# xbr.net
KiCad netlist of a schematic drawn in EAGLE
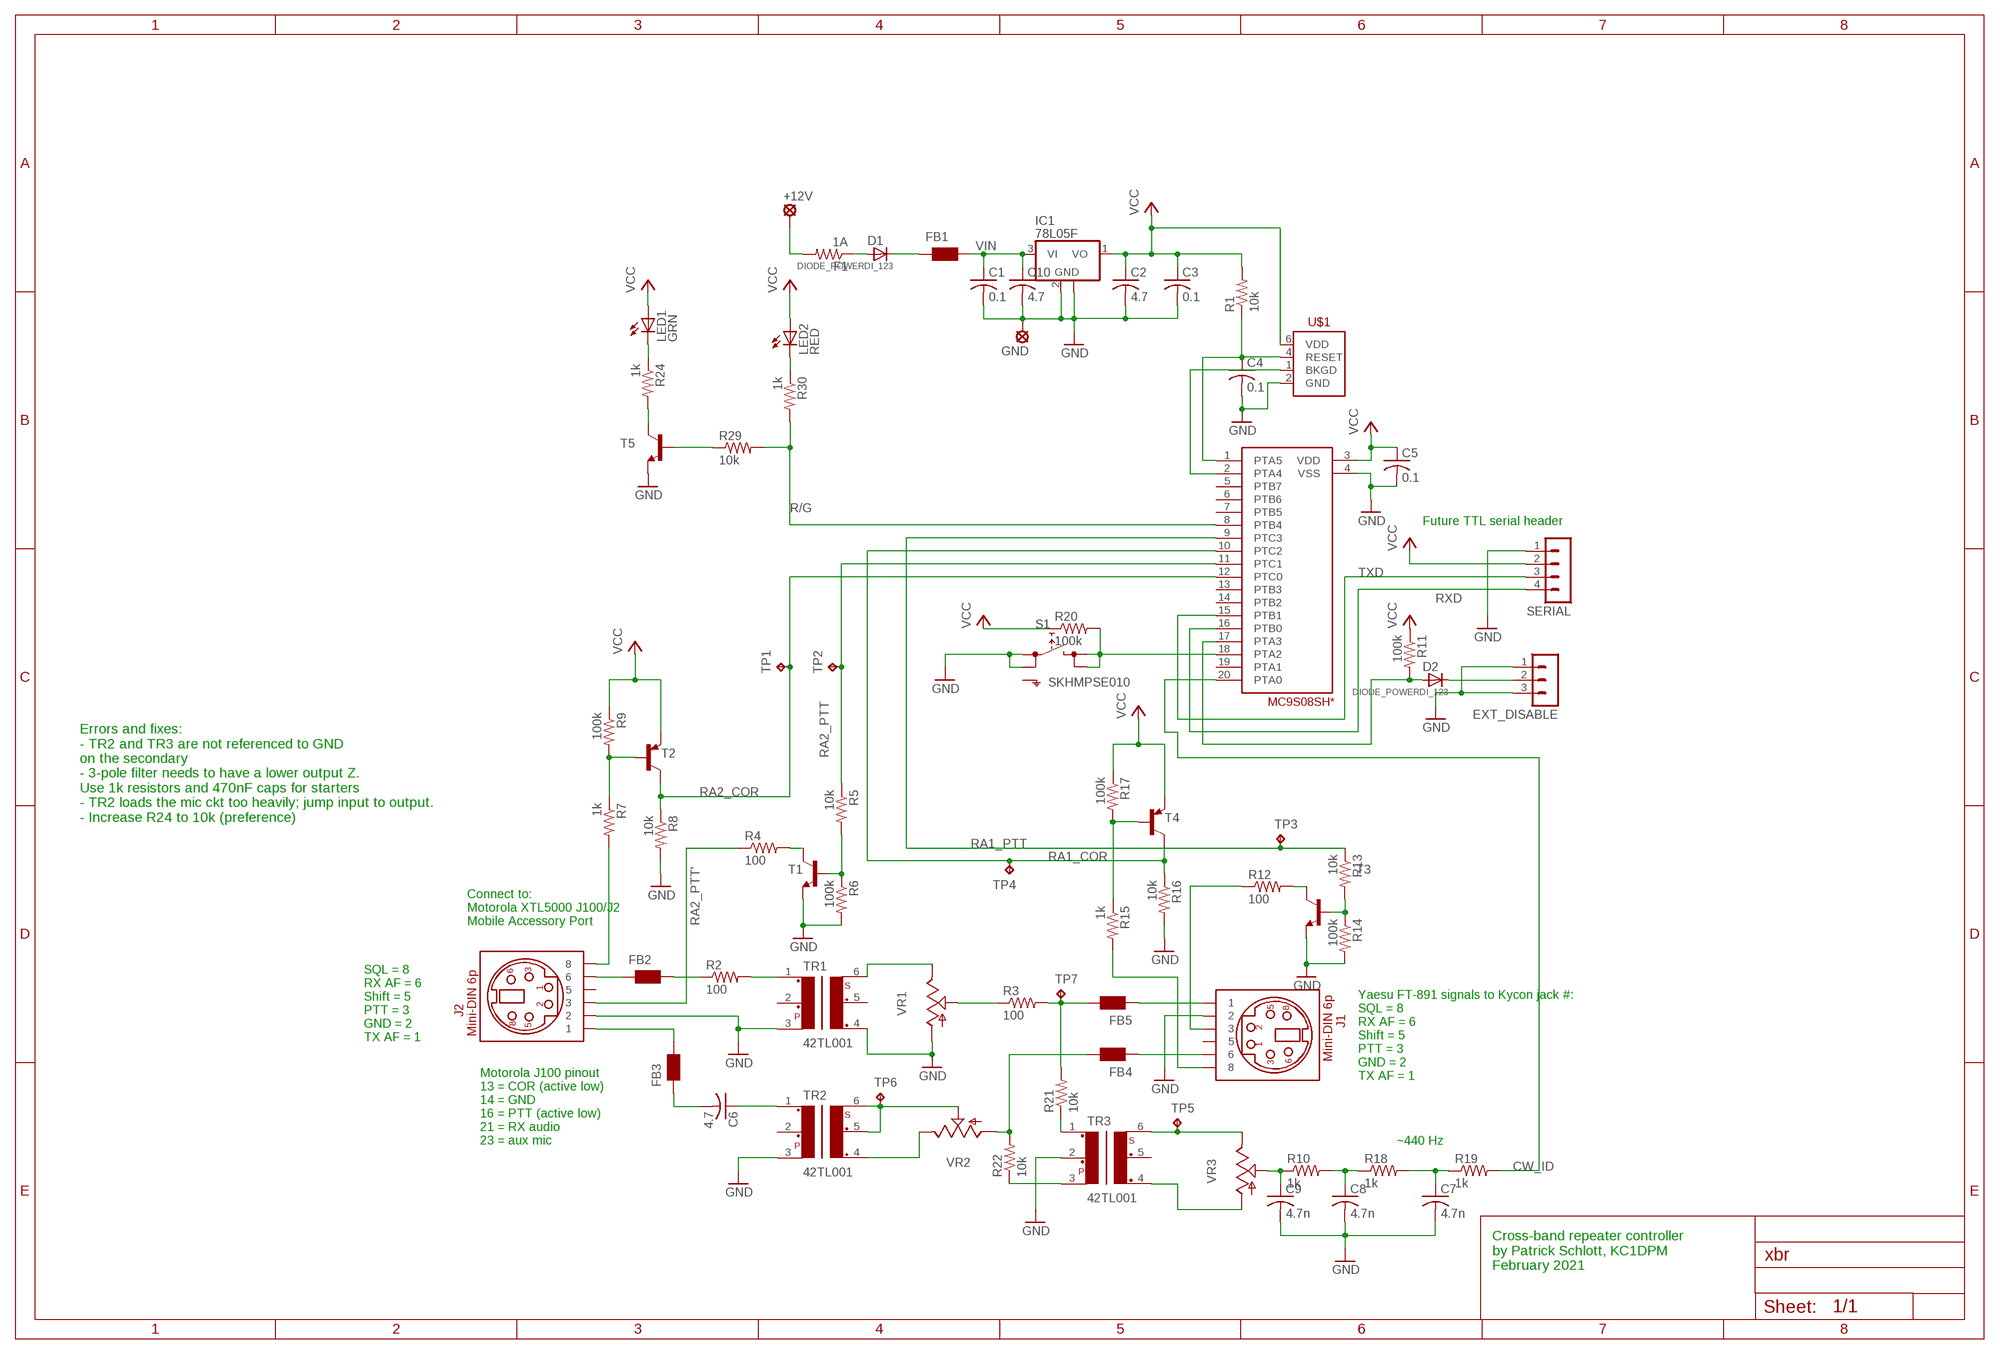
[diagram p0: schematic, sheet 1]

(export (version "E")
  (design (tool "Eeschema 10.0.6"))
  (components
    (comp (ref "+12V")
      (value "LSP10")
      (footprint "eagle-import:LSP10")
      (libsource (lib "eagle-import") (part "LSP10"))
    )
    (comp (ref "C1")
      (value "0.1")
      (footprint "eagle-import:C0603")
      (libsource (lib "eagle-import") (part "C-USC0603"))
    )
    (comp (ref "C2")
      (value "4.7")
      (footprint "eagle-import:C0805")
      (libsource (lib "eagle-import") (part "C-USC0805"))
    )
    (comp (ref "C3")
      (value "0.1")
      (footprint "eagle-import:C0603")
      (libsource (lib "eagle-import") (part "C-USC0603"))
    )
    (comp (ref "C4")
      (value "0.1")
      (footprint "eagle-import:C0603")
      (libsource (lib "eagle-import") (part "C-USC0603"))
    )
    (comp (ref "C5")
      (value "0.1")
      (footprint "eagle-import:C0603")
      (libsource (lib "eagle-import") (part "C-USC0603"))
    )
    (comp (ref "C6")
      (value "4.7")
      (footprint "eagle-import:C0805")
      (libsource (lib "eagle-import") (part "C-USC0805"))
    )
    (comp (ref "C7")
      (value "4.7n")
      (footprint "eagle-import:C0603")
      (libsource (lib "eagle-import") (part "C-USC0603"))
    )
    (comp (ref "C8")
      (value "4.7n")
      (footprint "eagle-import:C0603")
      (libsource (lib "eagle-import") (part "C-USC0603"))
    )
    (comp (ref "C9")
      (value "4.7n")
      (footprint "eagle-import:C0603")
      (libsource (lib "eagle-import") (part "C-USC0603"))
    )
    (comp (ref "C10")
      (value "4.7")
      (footprint "eagle-import:C0805")
      (libsource (lib "eagle-import") (part "C-USC0805"))
    )
    (comp (ref "D1")
      (value "DIODE_POWERDI_123")
      (footprint "eagle-import:POWERDI_123")
      (libsource (lib "eagle-import") (part "DIODE_POWERDI_123"))
    )
    (comp (ref "D2")
      (value "DIODE_POWERDI_123")
      (footprint "eagle-import:POWERDI_123")
      (libsource (lib "eagle-import") (part "DIODE_POWERDI_123"))
    )
    (comp (ref "EXT_DISABLE")
      (value "MA03-1")
      (footprint "eagle-import:MA03-1")
      (libsource (lib "eagle-import") (part "MA03-1"))
    )
    (comp (ref "F1")
      (value "1A")
      (footprint "eagle-import:R0603")
      (libsource (lib "eagle-import") (part "R-US_R0603"))
    )
    (comp (ref "FB1")
      (value "WE-CBF_0805")
      (footprint "eagle-import:0805")
      (libsource (lib "eagle-import") (part "WE-CBF_0805"))
    )
    (comp (ref "FB2")
      (value "WE-CBF_0805")
      (footprint "eagle-import:0805")
      (libsource (lib "eagle-import") (part "WE-CBF_0805"))
    )
    (comp (ref "FB3")
      (value "WE-CBF_0805")
      (footprint "eagle-import:0805")
      (libsource (lib "eagle-import") (part "WE-CBF_0805"))
    )
    (comp (ref "FB4")
      (value "WE-CBF_0805")
      (footprint "eagle-import:0805")
      (libsource (lib "eagle-import") (part "WE-CBF_0805"))
    )
    (comp (ref "FB5")
      (value "WE-CBF_0805")
      (footprint "eagle-import:0805")
      (libsource (lib "eagle-import") (part "WE-CBF_0805"))
    )
    (comp (ref "GND")
      (value "LSP10")
      (footprint "eagle-import:LSP10")
      (libsource (lib "eagle-import") (part "LSP10"))
    )
    (comp (ref "IC1")
      (value "78L05F")
      (footprint "eagle-import:SOT89")
      (libsource (lib "eagle-import") (part "78LF05"))
    )
    (comp (ref "J1")
      (value "MINIDIN-6P")
      (footprint "eagle-import:KMDTX-HT-6S-BSC")
      (libsource (lib "eagle-import") (part "MINIDIN-6P"))
    )
    (comp (ref "J2")
      (value "MINIDIN-6P")
      (footprint "eagle-import:KMDTX-HT-6S-BSC")
      (libsource (lib "eagle-import") (part "MINIDIN-6P"))
    )
    (comp (ref "LED1")
      (value "GRN")
      (footprint "eagle-import:CHIPLED_0603")
      (libsource (lib "eagle-import") (part "LEDCHIPLED_0603"))
    )
    (comp (ref "LED2")
      (value "RED")
      (footprint "eagle-import:CHIPLED_0805")
      (libsource (lib "eagle-import") (part "LEDCHIPLED_0805"))
    )
    (comp (ref "R1")
      (value "10k")
      (footprint "eagle-import:R0603")
      (libsource (lib "eagle-import") (part "R-US_R0603"))
    )
    (comp (ref "R2")
      (value "100")
      (footprint "eagle-import:R1206")
      (libsource (lib "eagle-import") (part "R-US_R1206"))
    )
    (comp (ref "R3")
      (value "100")
      (footprint "eagle-import:R1206")
      (libsource (lib "eagle-import") (part "R-US_R1206"))
    )
    (comp (ref "R4")
      (value "100")
      (footprint "eagle-import:R1206")
      (libsource (lib "eagle-import") (part "R-US_R1206"))
    )
    (comp (ref "R5")
      (value "10k")
      (footprint "eagle-import:R0603")
      (libsource (lib "eagle-import") (part "R-US_R0603"))
    )
    (comp (ref "R6")
      (value "100k")
      (footprint "eagle-import:R0603")
      (libsource (lib "eagle-import") (part "R-US_R0603"))
    )
    (comp (ref "R7")
      (value "1k")
      (footprint "eagle-import:R0603")
      (libsource (lib "eagle-import") (part "R-US_R0603"))
    )
    (comp (ref "R8")
      (value "10k")
      (footprint "eagle-import:R0603")
      (libsource (lib "eagle-import") (part "R-US_R0603"))
    )
    (comp (ref "R9")
      (value "100k")
      (footprint "eagle-import:R0603")
      (libsource (lib "eagle-import") (part "R-US_R0603"))
    )
    (comp (ref "R10")
      (value "1k")
      (footprint "eagle-import:R0603")
      (libsource (lib "eagle-import") (part "R-US_R0603"))
    )
    (comp (ref "R11")
      (value "100k")
      (footprint "eagle-import:R0603")
      (libsource (lib "eagle-import") (part "R-US_R0603"))
    )
    (comp (ref "R12")
      (value "100")
      (footprint "eagle-import:R1206")
      (libsource (lib "eagle-import") (part "R-US_R1206"))
    )
    (comp (ref "R13")
      (value "10k")
      (footprint "eagle-import:R0603")
      (libsource (lib "eagle-import") (part "R-US_R0603"))
    )
    (comp (ref "R14")
      (value "100k")
      (footprint "eagle-import:R0603")
      (libsource (lib "eagle-import") (part "R-US_R0603"))
    )
    (comp (ref "R15")
      (value "1k")
      (footprint "eagle-import:R0603")
      (libsource (lib "eagle-import") (part "R-US_R0603"))
    )
    (comp (ref "R16")
      (value "10k")
      (footprint "eagle-import:R0603")
      (libsource (lib "eagle-import") (part "R-US_R0603"))
    )
    (comp (ref "R17")
      (value "100k")
      (footprint "eagle-import:R0603")
      (libsource (lib "eagle-import") (part "R-US_R0603"))
    )
    (comp (ref "R18")
      (value "1k")
      (footprint "eagle-import:R0603")
      (libsource (lib "eagle-import") (part "R-US_R0603"))
    )
    (comp (ref "R19")
      (value "1k")
      (footprint "eagle-import:R0603")
      (libsource (lib "eagle-import") (part "R-US_R0603"))
    )
    (comp (ref "R20")
      (value "100k")
      (footprint "eagle-import:R0603")
      (libsource (lib "eagle-import") (part "R-US_R0603"))
    )
    (comp (ref "R21")
      (value "10k")
      (footprint "eagle-import:R0603")
      (libsource (lib "eagle-import") (part "R-US_R0603"))
    )
    (comp (ref "R22")
      (value "10k")
      (footprint "eagle-import:R0603")
      (libsource (lib "eagle-import") (part "R-US_R0603"))
    )
    (comp (ref "R24")
      (value "1k")
      (footprint "eagle-import:R0603")
      (libsource (lib "eagle-import") (part "R-US_R0603"))
    )
    (comp (ref "R29")
      (value "10k")
      (footprint "eagle-import:R0603")
      (libsource (lib "eagle-import") (part "R-US_R0603"))
    )
    (comp (ref "R30")
      (value "1k")
      (footprint "eagle-import:R0603")
      (libsource (lib "eagle-import") (part "R-US_R0603"))
    )
    (comp (ref "S1")
      (value "SKHMPSE010")
      (footprint "eagle-import:SKHMPXE010")
      (libsource (lib "eagle-import") (part "SKHMPE010S"))
    )
    (comp (ref "SERIAL")
      (value "MA04-1")
      (footprint "eagle-import:MA04-1")
      (libsource (lib "eagle-import") (part "MA04-1"))
    )
    (comp (ref "T1")
      (value "MMBT2222ALT1-NPN-SOT23-BEC")
      (footprint "eagle-import:SOT23-BEC")
      (libsource (lib "eagle-import") (part "-NPN-SOT23-BECMMBT2222ALT1"))
    )
    (comp (ref "T2")
      (value "MMBT3906LT1-PNP-SOT23-BEC")
      (footprint "eagle-import:SOT23-BEC")
      (libsource (lib "eagle-import") (part "-PNP-SOT23-BECMMBT3906LT1"))
    )
    (comp (ref "T3")
      (value "MMBT2222ALT1-NPN-SOT23-BEC")
      (footprint "eagle-import:SOT23-BEC")
      (libsource (lib "eagle-import") (part "-NPN-SOT23-BECMMBT2222ALT1"))
    )
    (comp (ref "T4")
      (value "MMBT3906LT1-PNP-SOT23-BEC")
      (footprint "eagle-import:SOT23-BEC")
      (libsource (lib "eagle-import") (part "-PNP-SOT23-BECMMBT3906LT1"))
    )
    (comp (ref "T5")
      (value "MMBT2222ALT1-NPN-SOT23-BEC")
      (footprint "eagle-import:SOT23-BEC")
      (libsource (lib "eagle-import") (part "-NPN-SOT23-BECMMBT2222ALT1"))
    )
    (comp (ref "TP1")
      (value "TPPAD1-13")
      (footprint "eagle-import:P1-13")
      (libsource (lib "eagle-import") (part "TPPAD1-13"))
    )
    (comp (ref "TP2")
      (value "TPPAD1-13")
      (footprint "eagle-import:P1-13")
      (libsource (lib "eagle-import") (part "TPPAD1-13"))
    )
    (comp (ref "TP3")
      (value "TPPAD1-13")
      (footprint "eagle-import:P1-13")
      (libsource (lib "eagle-import") (part "TPPAD1-13"))
    )
    (comp (ref "TP4")
      (value "TPPAD1-13")
      (footprint "eagle-import:P1-13")
      (libsource (lib "eagle-import") (part "TPPAD1-13"))
    )
    (comp (ref "TP5")
      (value "TPPAD1-13")
      (footprint "eagle-import:P1-13")
      (libsource (lib "eagle-import") (part "TPPAD1-13"))
    )
    (comp (ref "TP6")
      (value "TPPAD1-13")
      (footprint "eagle-import:P1-13")
      (libsource (lib "eagle-import") (part "TPPAD1-13"))
    )
    (comp (ref "TP7")
      (value "TPPAD1-13")
      (footprint "eagle-import:P1-13")
      (libsource (lib "eagle-import") (part "TPPAD1-13"))
    )
    (comp (ref "TR1")
      (value "42TL001")
      (footprint "eagle-import:42TL")
      (libsource (lib "eagle-import") (part "42T?L001"))
    )
    (comp (ref "TR2")
      (value "42TL001")
      (footprint "eagle-import:42TL")
      (libsource (lib "eagle-import") (part "42T?L001"))
    )
    (comp (ref "TR3")
      (value "42TL001")
      (footprint "eagle-import:42TL")
      (libsource (lib "eagle-import") (part "42T?L001"))
    )
    (comp (ref "U$1")
      (value "BDM_HEADER")
      (footprint "eagle-import:2X03")
      (libsource (lib "eagle-import") (part "BDM_HEADER"))
    )
    (comp (ref "U$2")
      (value "MC9S08SH")
      (footprint "eagle-import:PDIP-20")
      (libsource (lib "eagle-import") (part "MC9S08SH"))
    )
    (comp (ref "VR1")
      (value "TRIM_US-B64Y")
      (footprint "eagle-import:B64Y")
      (libsource (lib "eagle-import") (part "TRIM_US-B64Y"))
    )
    (comp (ref "VR2")
      (value "TRIM_US-B64Y")
      (footprint "eagle-import:B64Y")
      (libsource (lib "eagle-import") (part "TRIM_US-B64Y"))
    )
    (comp (ref "VR3")
      (value "TRIM_US-B64Y")
      (footprint "eagle-import:B64Y")
      (libsource (lib "eagle-import") (part "TRIM_US-B64Y"))
    )
  )
  (nets
    (net (code "1") (name "/CW_ID") (class "Default")
      (node (ref "R19") (pin "2") (pinfunction "2_2") (pintype "passive"))
      (node (ref "U$2") (pin "20") (pinfunction "PTA0_20") (pintype "bidirectional"))
    )
    (net (code "2") (name "/RA1_COR") (class "Default")
      (node (ref "R16") (pin "1") (pinfunction "1_1") (pintype "passive"))
      (node (ref "T4") (pin "C") (pinfunction "C_C") (pintype "passive"))
      (node (ref "TP4") (pin "TP") (pinfunction "TP_TP") (pintype "input"))
      (node (ref "U$2") (pin "10") (pinfunction "PTC2_10") (pintype "bidirectional"))
    )
    (net (code "3") (name "/RA1_PTT") (class "Default")
      (node (ref "R13") (pin "1") (pinfunction "1_1") (pintype "passive"))
      (node (ref "TP3") (pin "TP") (pinfunction "TP_TP") (pintype "input"))
      (node (ref "U$2") (pin "9") (pinfunction "PTC3_9") (pintype "bidirectional"))
    )
    (net (code "4") (name "/RA2_COR") (class "Default")
      (node (ref "R8") (pin "1") (pinfunction "1_1") (pintype "passive"))
      (node (ref "T2") (pin "C") (pinfunction "C_C") (pintype "passive"))
      (node (ref "TP1") (pin "TP") (pinfunction "TP_TP") (pintype "input"))
      (node (ref "U$2") (pin "12") (pinfunction "PTC0_12") (pintype "bidirectional"))
    )
    (net (code "5") (name "/RA2_PTT") (class "Default")
      (node (ref "R5") (pin "1") (pinfunction "1_1") (pintype "passive"))
      (node (ref "TP2") (pin "TP") (pinfunction "TP_TP") (pintype "input"))
      (node (ref "U$2") (pin "11") (pinfunction "PTC1_11") (pintype "bidirectional"))
    )
    (net (code "6") (name "/RA2_PTT'") (class "Default")
      (node (ref "J2") (pin "3-PTT") (pinfunction "3_3-PTT") (pintype "bidirectional"))
      (node (ref "R4") (pin "1") (pinfunction "1_1") (pintype "passive"))
    )
    (net (code "7") (name "/RXD") (class "Default")
      (node (ref "SERIAL") (pin "4") (pinfunction "4_4") (pintype "passive"))
      (node (ref "U$2") (pin "16") (pinfunction "PTB0_16") (pintype "bidirectional"))
    )
    (net (code "8") (name "/R{slash}G") (class "Default")
      (node (ref "R29") (pin "2") (pinfunction "2_2") (pintype "passive"))
      (node (ref "R30") (pin "2") (pinfunction "2_2") (pintype "passive"))
      (node (ref "U$2") (pin "8") (pinfunction "PTB4_8") (pintype "bidirectional"))
    )
    (net (code "9") (name "/TXD") (class "Default")
      (node (ref "SERIAL") (pin "3") (pinfunction "3_3") (pintype "passive"))
      (node (ref "U$2") (pin "15") (pinfunction "PTB1_15") (pintype "bidirectional"))
    )
    (net (code "10") (name "/VIN") (class "Default")
      (node (ref "C1") (pin "1") (pinfunction "1_1") (pintype "passive"))
      (node (ref "C10") (pin "1") (pinfunction "1_1") (pintype "passive"))
      (node (ref "FB1") (pin "2") (pinfunction "2_2") (pintype "passive"))
      (node (ref "IC1") (pin "3") (pinfunction "VI_3") (pintype "input"))
    )
    (net (code "11") (name "GND") (class "Default")
      (node (ref "C1") (pin "2") (pinfunction "2_2") (pintype "passive"))
      (node (ref "C10") (pin "2") (pinfunction "2_2") (pintype "passive"))
      (node (ref "C2") (pin "2") (pinfunction "2_2") (pintype "passive"))
      (node (ref "C3") (pin "2") (pinfunction "2_2") (pintype "passive"))
      (node (ref "C4") (pin "2") (pinfunction "2_2") (pintype "passive"))
      (node (ref "C5") (pin "2") (pinfunction "2_2") (pintype "passive"))
      (node (ref "C7") (pin "2") (pinfunction "2_2") (pintype "passive"))
      (node (ref "C8") (pin "2") (pinfunction "2_2") (pintype "passive"))
      (node (ref "C9") (pin "2") (pinfunction "2_2") (pintype "passive"))
      (node (ref "EXT_DISABLE") (pin "1") (pinfunction "1_1") (pintype "passive"))
      (node (ref "EXT_DISABLE") (pin "3") (pinfunction "3_3") (pintype "passive"))
      (node (ref "GND") (pin "MP") (pinfunction "MP_MP") (pintype "passive"))
      (node (ref "IC1") (pin "2") (pinfunction "GND_2") (pintype "passive"))
      (node (ref "IC1") (pin "2@1") (pinfunction "GND_2@1") (pintype "passive"))
      (node (ref "J1") (pin "2-GND") (pinfunction "2_2-GND") (pintype "bidirectional"))
      (node (ref "J2") (pin "2-GND") (pinfunction "2_2-GND") (pintype "bidirectional"))
      (node (ref "R14") (pin "2") (pinfunction "2_2") (pintype "passive"))
      (node (ref "R16") (pin "2") (pinfunction "2_2") (pintype "passive"))
      (node (ref "R6") (pin "2") (pinfunction "2_2") (pintype "passive"))
      (node (ref "R8") (pin "2") (pinfunction "2_2") (pintype "passive"))
      (node (ref "S1") (pin "1") (pinfunction "1.1_1") (pintype "passive"))
      (node (ref "S1") (pin "2") (pinfunction "1.2_2") (pintype "passive"))
      (node (ref "SERIAL") (pin "1") (pinfunction "1_1") (pintype "passive"))
      (node (ref "T1") (pin "E") (pinfunction "E_E") (pintype "passive"))
      (node (ref "T3") (pin "E") (pinfunction "E_E") (pintype "passive"))
      (node (ref "T5") (pin "E") (pinfunction "E_E") (pintype "passive"))
      (node (ref "TR1") (pin "3") (pinfunction "3_3") (pintype "passive"))
      (node (ref "TR1") (pin "4") (pinfunction "4_4") (pintype "passive"))
      (node (ref "TR2") (pin "3") (pinfunction "3_3") (pintype "passive"))
      (node (ref "TR3") (pin "2") (pinfunction "2_2") (pintype "passive"))
      (node (ref "U$1") (pin "2") (pinfunction "GND_2") (pintype "bidirectional"))
      (node (ref "U$2") (pin "4") (pinfunction "VSS_4") (pintype "bidirectional"))
      (node (ref "VR1") (pin "A") (pinfunction "A_A") (pintype "passive"))
    )
    (net (code "12") (name "Net-(+12V-PadMP)") (class "Default")
      (node (ref "+12V") (pin "MP") (pinfunction "MP_MP") (pintype "passive"))
      (node (ref "F1") (pin "2") (pinfunction "2_2") (pintype "passive"))
    )
    (net (code "13") (name "Net-(C6-Pad1)") (class "Default")
      (node (ref "C6") (pin "1") (pinfunction "1_1") (pintype "passive"))
      (node (ref "TR2") (pin "1") (pinfunction "1_1") (pintype "passive"))
    )
    (net (code "14") (name "Net-(C6-Pad2)") (class "Default")
      (node (ref "C6") (pin "2") (pinfunction "2_2") (pintype "passive"))
      (node (ref "FB3") (pin "1") (pinfunction "1_1") (pintype "passive"))
    )
    (net (code "15") (name "Net-(C7-Pad1)") (class "Default")
      (node (ref "C7") (pin "1") (pinfunction "1_1") (pintype "passive"))
      (node (ref "R18") (pin "2") (pinfunction "2_2") (pintype "passive"))
      (node (ref "R19") (pin "1") (pinfunction "1_1") (pintype "passive"))
    )
    (net (code "16") (name "Net-(C8-Pad1)") (class "Default")
      (node (ref "C8") (pin "1") (pinfunction "1_1") (pintype "passive"))
      (node (ref "R10") (pin "2") (pinfunction "2_2") (pintype "passive"))
      (node (ref "R18") (pin "1") (pinfunction "1_1") (pintype "passive"))
    )
    (net (code "17") (name "Net-(C9-Pad1)") (class "Default")
      (node (ref "C9") (pin "1") (pinfunction "1_1") (pintype "passive"))
      (node (ref "R10") (pin "1") (pinfunction "1_1") (pintype "passive"))
      (node (ref "VR3") (pin "S") (pinfunction "S_S") (pintype "passive"))
    )
    (net (code "18") (name "Net-(D1-C)") (class "Default")
      (node (ref "D1") (pin "K") (pinfunction "C_K") (pintype "passive"))
      (node (ref "FB1") (pin "1") (pinfunction "1_1") (pintype "passive"))
    )
    (net (code "19") (name "Net-(D1-PadA)") (class "Default")
      (node (ref "D1") (pin "A") (pinfunction "A_A") (pintype "passive"))
      (node (ref "F1") (pin "1") (pinfunction "1_1") (pintype "passive"))
    )
    (net (code "20") (name "Net-(D2-C)") (class "Default")
      (node (ref "D2") (pin "K") (pinfunction "C_K") (pintype "passive"))
      (node (ref "EXT_DISABLE") (pin "2") (pinfunction "2_2") (pintype "passive"))
    )
    (net (code "21") (name "Net-(FB2-Pad2)") (class "Default")
      (node (ref "FB2") (pin "2") (pinfunction "2_2") (pintype "passive"))
      (node (ref "R2") (pin "1") (pinfunction "1_1") (pintype "passive"))
    )
    (net (code "22") (name "Net-(FB4-Pad2)") (class "Default")
      (node (ref "FB4") (pin "2") (pinfunction "2_2") (pintype "passive"))
      (node (ref "R22") (pin "2") (pinfunction "2_2") (pintype "passive"))
      (node (ref "VR2") (pin "A") (pinfunction "A_A") (pintype "passive"))
    )
    (net (code "23") (name "Net-(FB5-Pad2)") (class "Default")
      (node (ref "FB5") (pin "2") (pinfunction "2_2") (pintype "passive"))
      (node (ref "R21") (pin "2") (pinfunction "2_2") (pintype "passive"))
      (node (ref "R3") (pin "2") (pinfunction "2_2") (pintype "passive"))
      (node (ref "TP7") (pin "TP") (pinfunction "TP_TP") (pintype "input"))
    )
    (net (code "24") (name "Net-(J1-1)") (class "Default")
      (node (ref "FB5") (pin "1") (pinfunction "1_1") (pintype "passive"))
      (node (ref "J1") (pin "1-DATA_IN") (pinfunction "1_1-DATA_IN") (pintype "bidirectional"))
    )
    (net (code "25") (name "Net-(J1-3)") (class "Default")
      (node (ref "J1") (pin "3-PTT") (pinfunction "3_3-PTT") (pintype "bidirectional"))
      (node (ref "R12") (pin "1") (pinfunction "1_1") (pintype "passive"))
    )
    (net (code "26") (name "Net-(J1-6)") (class "Default")
      (node (ref "FB4") (pin "1") (pinfunction "1_1") (pintype "passive"))
      (node (ref "J1") (pin "6-DATA_OUT") (pinfunction "6_6-DATA_OUT") (pintype "bidirectional"))
    )
    (net (code "27") (name "Net-(J1-8)") (class "Default")
      (node (ref "J1") (pin "8-SQL/COR") (pinfunction "8_8-SQL/COR") (pintype "bidirectional"))
      (node (ref "R15") (pin "2") (pinfunction "2_2") (pintype "passive"))
    )
    (net (code "28") (name "Net-(J2-1)") (class "Default")
      (node (ref "FB3") (pin "2") (pinfunction "2_2") (pintype "passive"))
      (node (ref "J2") (pin "1-DATA_IN") (pinfunction "1_1-DATA_IN") (pintype "bidirectional"))
    )
    (net (code "29") (name "Net-(J2-6)") (class "Default")
      (node (ref "FB2") (pin "1") (pinfunction "1_1") (pintype "passive"))
      (node (ref "J2") (pin "6-DATA_OUT") (pinfunction "6_6-DATA_OUT") (pintype "bidirectional"))
    )
    (net (code "30") (name "Net-(J2-8)") (class "Default")
      (node (ref "J2") (pin "8-SQL/COR") (pinfunction "8_8-SQL/COR") (pintype "bidirectional"))
      (node (ref "R7") (pin "2") (pinfunction "2_2") (pintype "passive"))
    )
    (net (code "31") (name "Net-(LED1-PadC)") (class "Default")
      (node (ref "LED1") (pin "C") (pinfunction "C_C") (pintype "passive"))
      (node (ref "R24") (pin "1") (pinfunction "1_1") (pintype "passive"))
    )
    (net (code "32") (name "Net-(LED2-PadC)") (class "Default")
      (node (ref "LED2") (pin "C") (pinfunction "C_C") (pintype "passive"))
      (node (ref "R30") (pin "1") (pinfunction "1_1") (pintype "passive"))
    )
    (net (code "33") (name "Net-(R2-Pad2)") (class "Default")
      (node (ref "R2") (pin "2") (pinfunction "2_2") (pintype "passive"))
      (node (ref "TR1") (pin "1") (pinfunction "1_1") (pintype "passive"))
    )
    (net (code "34") (name "Net-(R3-Pad1)") (class "Default")
      (node (ref "R3") (pin "1") (pinfunction "1_1") (pintype "passive"))
      (node (ref "VR1") (pin "S") (pinfunction "S_S") (pintype "passive"))
    )
    (net (code "35") (name "Net-(R4-Pad2)") (class "Default")
      (node (ref "R4") (pin "2") (pinfunction "2_2") (pintype "passive"))
      (node (ref "T1") (pin "C") (pinfunction "C_C") (pintype "passive"))
    )
    (net (code "36") (name "Net-(R5-Pad2)") (class "Default")
      (node (ref "R5") (pin "2") (pinfunction "2_2") (pintype "passive"))
      (node (ref "R6") (pin "1") (pinfunction "1_1") (pintype "passive"))
      (node (ref "T1") (pin "B") (pinfunction "B_B") (pintype "passive"))
    )
    (net (code "37") (name "Net-(R7-Pad1)") (class "Default")
      (node (ref "R7") (pin "1") (pinfunction "1_1") (pintype "passive"))
      (node (ref "R9") (pin "2") (pinfunction "2_2") (pintype "passive"))
      (node (ref "T2") (pin "B") (pinfunction "B_B") (pintype "passive"))
    )
    (net (code "38") (name "Net-(R12-Pad2)") (class "Default")
      (node (ref "R12") (pin "2") (pinfunction "2_2") (pintype "passive"))
      (node (ref "T3") (pin "C") (pinfunction "C_C") (pintype "passive"))
    )
    (net (code "39") (name "Net-(R13-Pad2)") (class "Default")
      (node (ref "R13") (pin "2") (pinfunction "2_2") (pintype "passive"))
      (node (ref "R14") (pin "1") (pinfunction "1_1") (pintype "passive"))
      (node (ref "T3") (pin "B") (pinfunction "B_B") (pintype "passive"))
    )
    (net (code "40") (name "Net-(R15-Pad1)") (class "Default")
      (node (ref "R15") (pin "1") (pinfunction "1_1") (pintype "passive"))
      (node (ref "R17") (pin "2") (pinfunction "2_2") (pintype "passive"))
      (node (ref "T4") (pin "B") (pinfunction "B_B") (pintype "passive"))
    )
    (net (code "41") (name "Net-(R21-Pad1)") (class "Default")
      (node (ref "R21") (pin "1") (pinfunction "1_1") (pintype "passive"))
      (node (ref "TR3") (pin "1") (pinfunction "1_1") (pintype "passive"))
    )
    (net (code "42") (name "Net-(R22-Pad1)") (class "Default")
      (node (ref "R22") (pin "1") (pinfunction "1_1") (pintype "passive"))
      (node (ref "TR3") (pin "3") (pinfunction "3_3") (pintype "passive"))
    )
    (net (code "43") (name "Net-(R24-Pad2)") (class "Default")
      (node (ref "R24") (pin "2") (pinfunction "2_2") (pintype "passive"))
      (node (ref "T5") (pin "C") (pinfunction "C_C") (pintype "passive"))
    )
    (net (code "44") (name "Net-(R29-Pad1)") (class "Default")
      (node (ref "R29") (pin "1") (pinfunction "1_1") (pintype "passive"))
      (node (ref "T5") (pin "B") (pinfunction "B_B") (pintype "passive"))
    )
    (net (code "45") (name "Net-(S1-2.1)") (class "Default")
      (node (ref "R20") (pin "2") (pinfunction "2_2") (pintype "passive"))
      (node (ref "S1") (pin "3") (pinfunction "2.1_3") (pintype "passive"))
      (node (ref "S1") (pin "4") (pinfunction "2.2_4") (pintype "passive"))
      (node (ref "U$2") (pin "18") (pinfunction "PTA2_18") (pintype "bidirectional"))
    )
    (net (code "46") (name "Net-(TP5-PadTP)") (class "Default")
      (node (ref "TP5") (pin "TP") (pinfunction "TP_TP") (pintype "input"))
      (node (ref "TR3") (pin "6") (pinfunction "6_6") (pintype "passive"))
      (node (ref "VR3") (pin "E") (pinfunction "E_E") (pintype "passive"))
    )
    (net (code "47") (name "Net-(TP6-PadTP)") (class "Default")
      (node (ref "TP6") (pin "TP") (pinfunction "TP_TP") (pintype "input"))
      (node (ref "TR2") (pin "5") (pinfunction "5_5") (pintype "passive"))
      (node (ref "TR2") (pin "6") (pinfunction "6_6") (pintype "passive"))
      (node (ref "VR2") (pin "S") (pinfunction "S_S") (pintype "passive"))
    )
    (net (code "48") (name "Net-(TR1-Pad6)") (class "Default")
      (node (ref "TR1") (pin "6") (pinfunction "6_6") (pintype "passive"))
      (node (ref "VR1") (pin "E") (pinfunction "E_E") (pintype "passive"))
    )
    (net (code "49") (name "Net-(TR2-Pad4)") (class "Default")
      (node (ref "TR2") (pin "4") (pinfunction "4_4") (pintype "passive"))
      (node (ref "VR2") (pin "E") (pinfunction "E_E") (pintype "passive"))
    )
    (net (code "50") (name "Net-(TR3-Pad4)") (class "Default")
      (node (ref "TR3") (pin "4") (pinfunction "4_4") (pintype "passive"))
      (node (ref "VR3") (pin "A") (pinfunction "A_A") (pintype "passive"))
    )
    (net (code "51") (name "Net-(U$1-BKGD)") (class "Default")
      (node (ref "U$1") (pin "1") (pinfunction "BKGD_1") (pintype "bidirectional"))
      (node (ref "U$2") (pin "2") (pinfunction "PTA4_2") (pintype "bidirectional"))
    )
    (net (code "52") (name "Net-(U$1-RESET)") (class "Default")
      (node (ref "C4") (pin "1") (pinfunction "1_1") (pintype "passive"))
      (node (ref "R1") (pin "1") (pinfunction "1_1") (pintype "passive"))
      (node (ref "U$1") (pin "4") (pinfunction "RESET_4") (pintype "bidirectional"))
      (node (ref "U$2") (pin "1") (pinfunction "PTA5_1") (pintype "bidirectional"))
    )
    (net (code "53") (name "Net-(U$2-PTA3)") (class "Default")
      (node (ref "D2") (pin "A") (pinfunction "A_A") (pintype "passive"))
      (node (ref "R11") (pin "2") (pinfunction "2_2") (pintype "passive"))
      (node (ref "U$2") (pin "17") (pinfunction "PTA3_17") (pintype "bidirectional"))
    )
    (net (code "54") (name "VCC") (class "Default")
      (node (ref "C2") (pin "1") (pinfunction "1_1") (pintype "passive"))
      (node (ref "C3") (pin "1") (pinfunction "1_1") (pintype "passive"))
      (node (ref "C5") (pin "1") (pinfunction "1_1") (pintype "passive"))
      (node (ref "IC1") (pin "1") (pinfunction "VO_1") (pintype "passive"))
      (node (ref "LED1") (pin "A") (pinfunction "A_A") (pintype "passive"))
      (node (ref "LED2") (pin "A") (pinfunction "A_A") (pintype "passive"))
      (node (ref "R1") (pin "2") (pinfunction "2_2") (pintype "passive"))
      (node (ref "R11") (pin "1") (pinfunction "1_1") (pintype "passive"))
      (node (ref "R17") (pin "1") (pinfunction "1_1") (pintype "passive"))
      (node (ref "R20") (pin "1") (pinfunction "1_1") (pintype "passive"))
      (node (ref "R9") (pin "1") (pinfunction "1_1") (pintype "passive"))
      (node (ref "SERIAL") (pin "2") (pinfunction "2_2") (pintype "passive"))
      (node (ref "T2") (pin "E") (pinfunction "E_E") (pintype "passive"))
      (node (ref "T4") (pin "E") (pinfunction "E_E") (pintype "passive"))
      (node (ref "U$1") (pin "6") (pinfunction "VDD_6") (pintype "bidirectional"))
      (node (ref "U$2") (pin "3") (pinfunction "VDD_3") (pintype "bidirectional"))
    )
    (net (code "55") (name "unconnected-(J1-5-Pad5-SHIFT(FSK))") (class "Default")
      (node (ref "J1") (pin "5-SHIFT(FSK)") (pinfunction "5_5-SHIFT(FSK)") (pintype "bidirectional"))
    )
    (net (code "56") (name "unconnected-(J2-5-Pad5-SHIFT(FSK))") (class "Default")
      (node (ref "J2") (pin "5-SHIFT(FSK)") (pinfunction "5_5-SHIFT(FSK)") (pintype "bidirectional"))
    )
    (net (code "57") (name "unconnected-(S1-SH-Pad5)") (class "Default")
      (node (ref "S1") (pin "5") (pinfunction "SH_5") (pintype "passive"))
    )
    (net (code "58") (name "unconnected-(TR1-Pad2)") (class "Default")
      (node (ref "TR1") (pin "2") (pinfunction "2_2") (pintype "passive"))
    )
    (net (code "59") (name "unconnected-(TR1-Pad5)") (class "Default")
      (node (ref "TR1") (pin "5") (pinfunction "5_5") (pintype "passive"))
    )
    (net (code "60") (name "unconnected-(TR2-Pad2)") (class "Default")
      (node (ref "TR2") (pin "2") (pinfunction "2_2") (pintype "passive"))
    )
    (net (code "61") (name "unconnected-(TR3-Pad5)") (class "Default")
      (node (ref "TR3") (pin "5") (pinfunction "5_5") (pintype "passive"))
    )
    (net (code "62") (name "unconnected-(U$2-PTA1-Pad19)") (class "Default")
      (node (ref "U$2") (pin "19") (pinfunction "PTA1_19") (pintype "bidirectional"))
    )
    (net (code "63") (name "unconnected-(U$2-PTB2-Pad14)") (class "Default")
      (node (ref "U$2") (pin "14") (pinfunction "PTB2_14") (pintype "bidirectional"))
    )
    (net (code "64") (name "unconnected-(U$2-PTB3-Pad13)") (class "Default")
      (node (ref "U$2") (pin "13") (pinfunction "PTB3_13") (pintype "bidirectional"))
    )
    (net (code "65") (name "unconnected-(U$2-PTB5-Pad7)") (class "Default")
      (node (ref "U$2") (pin "7") (pinfunction "PTB5_7") (pintype "bidirectional"))
    )
    (net (code "66") (name "unconnected-(U$2-PTB6-Pad6)") (class "Default")
      (node (ref "U$2") (pin "6") (pinfunction "PTB6_6") (pintype "bidirectional"))
    )
    (net (code "67") (name "unconnected-(U$2-PTB7-Pad5)") (class "Default")
      (node (ref "U$2") (pin "5") (pinfunction "PTB7_5") (pintype "bidirectional"))
    )
  )
)
